# Tugas_Day_0-_William_Chandra.net
KiCad netlist of a schematic drawn in EAGLE
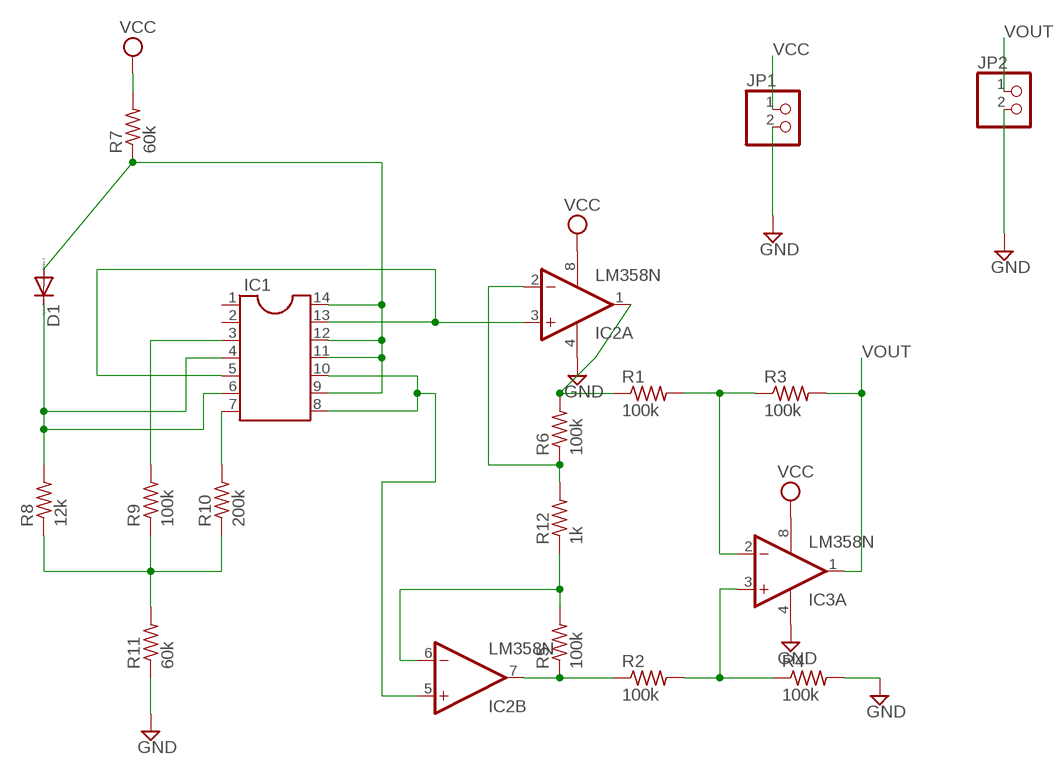
[diagram p0: schematic, sheet 1]

(export (version "E")
  (design (tool "Eeschema 10.0.6"))
  (components
    (comp (ref "D1")
      (value "DIODE-D-7.5")
      (footprint "eagle-import:D-7.5")
      (libsource (lib "eagle-import") (part "DIODE-D-7.5"))
    )
    (comp (ref "IC1")
      (value "DIL14")
      (footprint "eagle-import:DIL14")
      (libsource (lib "eagle-import") (part "DIL14"))
    )
    (comp (ref "IC2")
      (value "LM358N")
      (footprint "eagle-import:DIL08")
      (libsource (lib "eagle-import") (part "LM358N"))
    )
    (comp (ref "IC3")
      (value "LM358N")
      (footprint "eagle-import:DIL08")
      (libsource (lib "eagle-import") (part "LM358N"))
    )
    (comp (ref "JP1")
      (value "PINHD-1X2")
      (footprint "eagle-import:1X02")
      (libsource (lib "eagle-import") (part "PINHD-1X2"))
    )
    (comp (ref "JP2")
      (value "PINHD-1X2")
      (footprint "eagle-import:1X02")
      (libsource (lib "eagle-import") (part "PINHD-1X2"))
    )
    (comp (ref "R1")
      (value "100k")
      (footprint "eagle-import:0207_7")
      (libsource (lib "eagle-import") (part "R-US_0207/7"))
    )
    (comp (ref "R2")
      (value "100k")
      (footprint "eagle-import:0207_7")
      (libsource (lib "eagle-import") (part "R-US_0207/7"))
    )
    (comp (ref "R3")
      (value "100k")
      (footprint "eagle-import:0207_7")
      (libsource (lib "eagle-import") (part "R-US_0207/7"))
    )
    (comp (ref "R4")
      (value "100k")
      (footprint "eagle-import:0207_7")
      (libsource (lib "eagle-import") (part "R-US_0207/7"))
    )
    (comp (ref "R5")
      (value "100k")
      (footprint "eagle-import:0207_7")
      (libsource (lib "eagle-import") (part "R-US_0207/7"))
    )
    (comp (ref "R6")
      (value "100k")
      (footprint "eagle-import:0207_7")
      (libsource (lib "eagle-import") (part "R-US_0207/7"))
    )
    (comp (ref "R7")
      (value "60k")
      (footprint "eagle-import:0207_7")
      (libsource (lib "eagle-import") (part "R-US_0207/7"))
    )
    (comp (ref "R8")
      (value "12k")
      (footprint "eagle-import:0207_7")
      (libsource (lib "eagle-import") (part "R-US_0207/7"))
    )
    (comp (ref "R9")
      (value "100k")
      (footprint "eagle-import:0207_7")
      (libsource (lib "eagle-import") (part "R-US_0207/7"))
    )
    (comp (ref "R10")
      (value "200k")
      (footprint "eagle-import:0207_7")
      (libsource (lib "eagle-import") (part "R-US_0207/7"))
    )
    (comp (ref "R11")
      (value "60k")
      (footprint "eagle-import:0207_7")
      (libsource (lib "eagle-import") (part "R-US_0207/7"))
    )
    (comp (ref "R12")
      (value "1k")
      (footprint "eagle-import:0207_7")
      (libsource (lib "eagle-import") (part "R-US_0207/7"))
    )
  )
  (nets
    (net (code "1") (name "/VOUT") (class "Default")
      (node (ref "IC3") (pin "1") (pinfunction "OUT_1") (pintype "output"))
      (node (ref "JP2") (pin "1") (pinfunction "1_1") (pintype "passive"))
      (node (ref "R3") (pin "2") (pinfunction "2_2") (pintype "passive"))
    )
    (net (code "2") (name "GND") (class "Default")
      (node (ref "IC2") (pin "4") (pinfunction "V-_4") (pintype "power_in"))
      (node (ref "IC3") (pin "4") (pinfunction "V-_4") (pintype "power_in"))
      (node (ref "JP1") (pin "2") (pinfunction "2_2") (pintype "passive"))
      (node (ref "JP2") (pin "2") (pinfunction "2_2") (pintype "passive"))
      (node (ref "R11") (pin "1") (pinfunction "1_1") (pintype "passive"))
      (node (ref "R4") (pin "2") (pinfunction "2_2") (pintype "passive"))
    )
    (net (code "3") (name "Net-(D1-PadA)") (class "Default")
      (node (ref "D1") (pin "A") (pinfunction "A_A") (pintype "passive"))
      (node (ref "IC1") (pin "11") (pinfunction "11_11") (pintype "passive"))
      (node (ref "IC1") (pin "12") (pinfunction "12_12") (pintype "passive"))
      (node (ref "IC1") (pin "14") (pinfunction "14_14") (pintype "passive"))
      (node (ref "IC1") (pin "9") (pinfunction "9_9") (pintype "passive"))
      (node (ref "R7") (pin "1") (pinfunction "1_1") (pintype "passive"))
    )
    (net (code "4") (name "Net-(D1-PadC)") (class "Default")
      (node (ref "D1") (pin "C") (pinfunction "C_C") (pintype "passive"))
      (node (ref "IC1") (pin "4") (pinfunction "4_4") (pintype "passive"))
      (node (ref "IC1") (pin "6") (pinfunction "6_6") (pintype "passive"))
      (node (ref "R8") (pin "2") (pinfunction "2_2") (pintype "passive"))
    )
    (net (code "5") (name "Net-(IC1-Pad3)") (class "Default")
      (node (ref "IC1") (pin "3") (pinfunction "3_3") (pintype "passive"))
      (node (ref "R9") (pin "2") (pinfunction "2_2") (pintype "passive"))
    )
    (net (code "6") (name "Net-(IC1-Pad7)") (class "Default")
      (node (ref "IC1") (pin "7") (pinfunction "7_7") (pintype "passive"))
      (node (ref "R10") (pin "2") (pinfunction "2_2") (pintype "passive"))
    )
    (net (code "7") (name "Net-(IC2A-+IN)") (class "Default")
      (node (ref "IC1") (pin "13") (pinfunction "13_13") (pintype "passive"))
      (node (ref "IC1") (pin "5") (pinfunction "5_5") (pintype "passive"))
      (node (ref "IC2") (pin "3") (pinfunction "+IN_3") (pintype "input"))
    )
    (net (code "8") (name "Net-(IC2A--IN)") (class "Default")
      (node (ref "IC2") (pin "2") (pinfunction "-IN_2") (pintype "input"))
      (node (ref "R12") (pin "2") (pinfunction "2_2") (pintype "passive"))
      (node (ref "R6") (pin "1") (pinfunction "1_1") (pintype "passive"))
    )
    (net (code "9") (name "Net-(IC2A-OUT)") (class "Default")
      (node (ref "IC2") (pin "1") (pinfunction "OUT_1") (pintype "output"))
      (node (ref "R1") (pin "1") (pinfunction "1_1") (pintype "passive"))
      (node (ref "R6") (pin "2") (pinfunction "2_2") (pintype "passive"))
    )
    (net (code "10") (name "Net-(IC2B-+IN)") (class "Default")
      (node (ref "IC1") (pin "10") (pinfunction "10_10") (pintype "passive"))
      (node (ref "IC1") (pin "8") (pinfunction "8_8") (pintype "passive"))
      (node (ref "IC2") (pin "5") (pinfunction "+IN_5") (pintype "input"))
    )
    (net (code "11") (name "Net-(IC2B--IN)") (class "Default")
      (node (ref "IC2") (pin "6") (pinfunction "-IN_6") (pintype "input"))
      (node (ref "R12") (pin "1") (pinfunction "1_1") (pintype "passive"))
      (node (ref "R5") (pin "2") (pinfunction "2_2") (pintype "passive"))
    )
    (net (code "12") (name "Net-(IC2B-OUT)") (class "Default")
      (node (ref "IC2") (pin "7") (pinfunction "OUT_7") (pintype "output"))
      (node (ref "R2") (pin "1") (pinfunction "1_1") (pintype "passive"))
      (node (ref "R5") (pin "1") (pinfunction "1_1") (pintype "passive"))
    )
    (net (code "13") (name "Net-(IC3A-+IN)") (class "Default")
      (node (ref "IC3") (pin "3") (pinfunction "+IN_3") (pintype "input"))
      (node (ref "R2") (pin "2") (pinfunction "2_2") (pintype "passive"))
      (node (ref "R4") (pin "1") (pinfunction "1_1") (pintype "passive"))
    )
    (net (code "14") (name "Net-(IC3A--IN)") (class "Default")
      (node (ref "IC3") (pin "2") (pinfunction "-IN_2") (pintype "input"))
      (node (ref "R1") (pin "2") (pinfunction "2_2") (pintype "passive"))
      (node (ref "R3") (pin "1") (pinfunction "1_1") (pintype "passive"))
    )
    (net (code "15") (name "Net-(R10-Pad1)") (class "Default")
      (node (ref "R10") (pin "1") (pinfunction "1_1") (pintype "passive"))
      (node (ref "R11") (pin "2") (pinfunction "2_2") (pintype "passive"))
      (node (ref "R8") (pin "1") (pinfunction "1_1") (pintype "passive"))
      (node (ref "R9") (pin "1") (pinfunction "1_1") (pintype "passive"))
    )
    (net (code "16") (name "VCC") (class "Default")
      (node (ref "IC2") (pin "8") (pinfunction "V+_8") (pintype "power_in"))
      (node (ref "IC3") (pin "8") (pinfunction "V+_8") (pintype "power_in"))
      (node (ref "JP1") (pin "1") (pinfunction "1_1") (pintype "passive"))
      (node (ref "R7") (pin "2") (pinfunction "2_2") (pintype "passive"))
    )
    (net (code "17") (name "unconnected-(IC1-Pad1)") (class "Default")
      (node (ref "IC1") (pin "1") (pinfunction "1_1") (pintype "passive"))
    )
    (net (code "18") (name "unconnected-(IC1-Pad2)") (class "Default")
      (node (ref "IC1") (pin "2") (pinfunction "2_2") (pintype "passive"))
    )
  )
)
